# mv_cct.net
KiCad netlist of a schematic drawn in Altium Designer
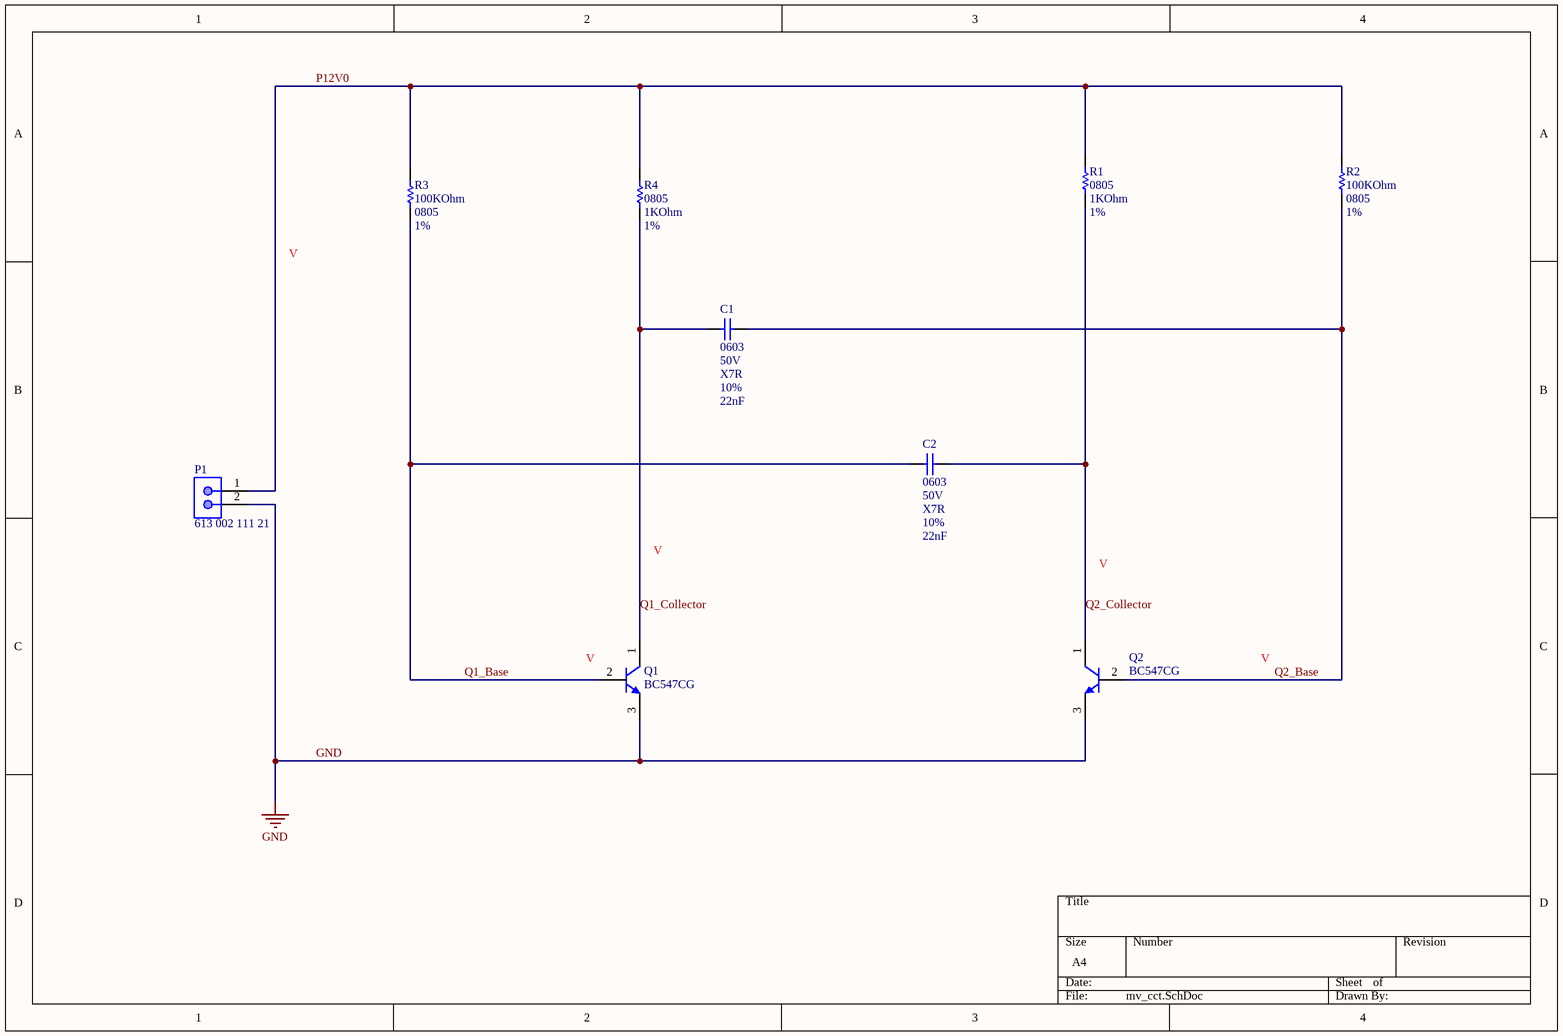
[diagram p0: mv_cct.SchDoc]

(export (version "E")
  (design (tool "Eeschema 10.0.6"))
  (components
    (comp (ref "C1")
      (value "CC0603KRX7R9BB223")
      (footprint "CAPC1608X90X40ML10T20")
      (description "Chip Capacitor, 22 nF, +/- 10%, 50 V, -55 to 125 degC, 0603 (1608 Metric), RoHS, Tape and Reel")
      (fields
        (field (name "CASE CODE (IMPERIAL)") "0603")
        (field (name "MANUFACTURER") "Yageo")
        (field (name "VOLTAGE RATING (DC)") "50V")
        (field (name "DIELECTRIC") "X7R")
        (field (name "TOLERANCE") "10%")
        (field (name "CAPACITANCE") "22nF")
      )
      (libsource (lib "Altium Content Vault") (part "CAP-NP-2"))
    )
    (comp (ref "C2")
      (value "CC0603KRX7R9BB223")
      (footprint "CAPC1608X90X40ML10T20")
      (description "Chip Capacitor, 22 nF, +/- 10%, 50 V, -55 to 125 degC, 0603 (1608 Metric), RoHS, Tape and Reel")
      (fields
        (field (name "CASE CODE (IMPERIAL)") "0603")
        (field (name "MANUFACTURER") "Yageo")
        (field (name "VOLTAGE RATING (DC)") "50V")
        (field (name "DIELECTRIC") "X7R")
        (field (name "TOLERANCE") "10%")
        (field (name "CAPACITANCE") "22nF")
      )
      (libsource (lib "Altium Content Vault") (part "CAP-NP-2"))
    )
    (comp (ref "P1")
      (value "613 002 111 21")
      (footprint "WE-61300211121_V")
      (libsource (lib "Altium Content Vault") (part "CN-1P-M-R2"))
    )
    (comp (ref "Q1")
      (value "BC547CG")
      (footprint "ONSC-TO-92-3-29-11")
      (description "Amplifier Transistor, NPN Silicon, 3-Pin TO-92, Pb-Free, Bulk Box")
      (fields (field (name "MANUFACTURER") "On Semiconductor"))
      (libsource (lib "Altium Content Vault") (part "ONSC-NPN-C1B2E3-3"))
    )
    (comp (ref "Q2")
      (value "BC547CG")
      (footprint "ONSC-TO-92-3-29-11")
      (description "Amplifier Transistor, NPN Silicon, 3-Pin TO-92, Pb-Free, Bulk Box")
      (fields (field (name "MANUFACTURER") "On Semiconductor"))
      (libsource (lib "Altium Content Vault") (part "ONSC-NPN-C1B2E3-3"))
    )
    (comp (ref "R1")
      (value "RC0805FR-071KL")
      (footprint "RESC2013X60X35ML10T20")
      (description "Chip Resistor, 1 KOhm, +/- 1%, 125 mW, -55 to 155 degC, 0805 (2012 Metric), RoHS, Tape and Reel")
      (fields
        (field (name "CASE/PACKAGE") "0805")
        (field (name "RESISTANCE") "1KOhm")
        (field (name "TOLERANCE") "1%")
        (field (name "MANUFACTURER") "Yageo")
      )
      (libsource (lib "Altium Content Vault") (part "RES-2"))
    )
    (comp (ref "R2")
      (value "RC0805FR-07100KL")
      (footprint "RESC2013X60X35ML10T20")
      (description "Chip Resistor, 100 KOhm, +/- 1%, 0.125 W, -55 to 155 degC, 0805 (2012 Metric), RoHS, Tape and Reel")
      (fields
        (field (name "MANUFACTURER") "Yageo")
        (field (name "RESISTANCE") "100KOhm")
        (field (name "CASE/PACKAGE") "0805")
        (field (name "TOLERANCE") "1%")
      )
      (libsource (lib "Altium Content Vault") (part "RES-2"))
    )
    (comp (ref "R3")
      (value "RC0805FR-07100KL")
      (footprint "RESC2013X60X35ML10T20")
      (description "Chip Resistor, 100 KOhm, +/- 1%, 0.125 W, -55 to 155 degC, 0805 (2012 Metric), RoHS, Tape and Reel")
      (fields
        (field (name "MANUFACTURER") "Yageo")
        (field (name "RESISTANCE") "100KOhm")
        (field (name "CASE/PACKAGE") "0805")
        (field (name "TOLERANCE") "1%")
      )
      (libsource (lib "Altium Content Vault") (part "RES-2"))
    )
    (comp (ref "R4")
      (value "RC0805FR-071KL")
      (footprint "RESC2013X60X35ML10T20")
      (description "Chip Resistor, 1 KOhm, +/- 1%, 125 mW, -55 to 155 degC, 0805 (2012 Metric), RoHS, Tape and Reel")
      (fields
        (field (name "CASE/PACKAGE") "0805")
        (field (name "RESISTANCE") "1KOhm")
        (field (name "TOLERANCE") "1%")
        (field (name "MANUFACTURER") "Yageo")
      )
      (libsource (lib "Altium Content Vault") (part "RES-2"))
    )
  )
  (nets
    (net (code "1") (name "/P12V0") (class "Default")
      (node (ref "P1") (pin "1") (pinfunction "1_1") (pintype "passive"))
      (node (ref "R1") (pin "2") (pinfunction "2_2") (pintype "passive"))
      (node (ref "R2") (pin "2") (pinfunction "2_2") (pintype "passive"))
      (node (ref "R3") (pin "2") (pinfunction "2_2") (pintype "passive"))
      (node (ref "R4") (pin "2") (pinfunction "2_2") (pintype "passive"))
    )
    (net (code "2") (name "/Q1_Base") (class "Default")
      (node (ref "C2") (pin "1") (pinfunction "1_1") (pintype "passive"))
      (node (ref "Q1") (pin "2") (pinfunction "B_2") (pintype "passive"))
      (node (ref "R3") (pin "1") (pinfunction "1_1") (pintype "passive"))
    )
    (net (code "3") (name "/Q1_Collector") (class "Default")
      (node (ref "C1") (pin "1") (pinfunction "1_1") (pintype "passive"))
      (node (ref "Q1") (pin "1") (pinfunction "C_1") (pintype "passive"))
      (node (ref "R4") (pin "1") (pinfunction "1_1") (pintype "passive"))
    )
    (net (code "4") (name "/Q2_Base") (class "Default")
      (node (ref "C1") (pin "2") (pinfunction "2_2") (pintype "passive"))
      (node (ref "Q2") (pin "2") (pinfunction "B_2") (pintype "passive"))
      (node (ref "R2") (pin "1") (pinfunction "1_1") (pintype "passive"))
    )
    (net (code "5") (name "/Q2_Collector") (class "Default")
      (node (ref "C2") (pin "2") (pinfunction "2_2") (pintype "passive"))
      (node (ref "Q2") (pin "1") (pinfunction "C_1") (pintype "passive"))
      (node (ref "R1") (pin "1") (pinfunction "1_1") (pintype "passive"))
    )
    (net (code "6") (name "GND") (class "Default")
      (node (ref "P1") (pin "2") (pinfunction "2_2") (pintype "passive"))
      (node (ref "Q1") (pin "3") (pinfunction "E_3") (pintype "passive"))
      (node (ref "Q2") (pin "3") (pinfunction "E_3") (pintype "passive"))
    )
  )
)
